# SDVX.net
KiCad netlist of a schematic drawn in Altium Designer
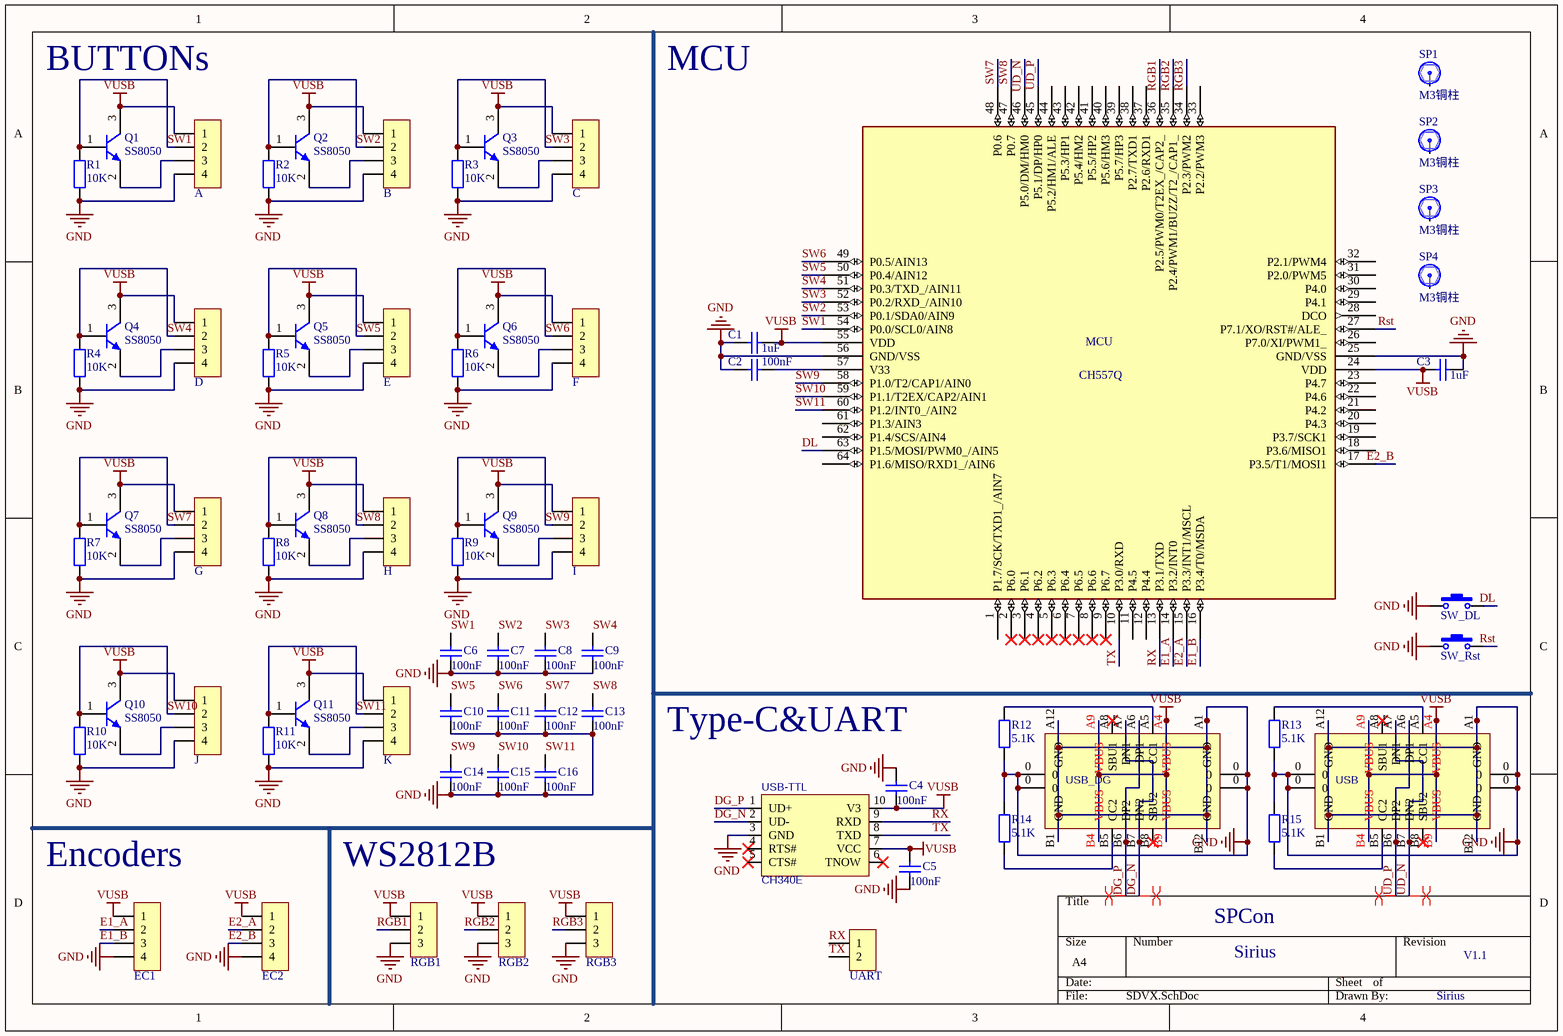
[diagram p0: SDVX.SchDoc]

(export (version "E")
  (design (tool "Eeschema 10.0.6"))
  (components
    (comp (ref "A")
      (value "HDR-1X4")
      (footprint "XH2.54-WI-4P")
      (description "4P接插件")
      (libsource (lib "5.5 - 2.54mm(100mil)连接器(XH2.54)") (part "Header 4"))
    )
    (comp (ref "B")
      (value "HDR-1X4")
      (footprint "XH2.54-WI-4P")
      (description "4P接插件")
      (libsource (lib "5.5 - 2.54mm(100mil)连接器(XH2.54)") (part "Header 4"))
    )
    (comp (ref "C")
      (value "HDR-1X4")
      (footprint "XH2.54-WI-4P")
      (description "4P接插件")
      (libsource (lib "5.5 - 2.54mm(100mil)连接器(XH2.54)") (part "Header 4"))
    )
    (comp (ref "C1")
      (value "1uF")
      (footprint "C0603_L")
      (description "贴片电容")
      (libsource (lib "0.1 - 电阻-电容-电感-电位器") (part "C"))
    )
    (comp (ref "C2")
      (value "100nF")
      (footprint "C0603_L")
      (description "贴片电容")
      (libsource (lib "0.1 - 电阻-电容-电感-电位器") (part "C"))
    )
    (comp (ref "C3")
      (value "1uF")
      (footprint "C0603_L")
      (description "贴片电容")
      (libsource (lib "0.1 - 电阻-电容-电感-电位器") (part "C"))
    )
    (comp (ref "C4")
      (value "100nF")
      (footprint "C0603_L")
      (description "贴片电容")
      (libsource (lib "0.1 - 电阻-电容-电感-电位器") (part "C"))
    )
    (comp (ref "C5")
      (value "100nF")
      (footprint "C0603_L")
      (description "贴片电容")
      (libsource (lib "0.1 - 电阻-电容-电感-电位器") (part "C"))
    )
    (comp (ref "C6")
      (value "100nF")
      (footprint "C0603_L")
      (description "贴片电容")
      (libsource (lib "0.1 - 电阻-电容-电感-电位器") (part "C"))
    )
    (comp (ref "C7")
      (value "100nF")
      (footprint "C0603_L")
      (description "贴片电容")
      (libsource (lib "0.1 - 电阻-电容-电感-电位器") (part "C"))
    )
    (comp (ref "C8")
      (value "100nF")
      (footprint "C0603_L")
      (description "贴片电容")
      (libsource (lib "0.1 - 电阻-电容-电感-电位器") (part "C"))
    )
    (comp (ref "C9")
      (value "100nF")
      (footprint "C0603_L")
      (description "贴片电容")
      (libsource (lib "0.1 - 电阻-电容-电感-电位器") (part "C"))
    )
    (comp (ref "C10")
      (value "100nF")
      (footprint "C0603_L")
      (description "贴片电容")
      (libsource (lib "0.1 - 电阻-电容-电感-电位器") (part "C"))
    )
    (comp (ref "C11")
      (value "100nF")
      (footprint "C0603_L")
      (description "贴片电容")
      (libsource (lib "0.1 - 电阻-电容-电感-电位器") (part "C"))
    )
    (comp (ref "C12")
      (value "100nF")
      (footprint "C0603_L")
      (description "贴片电容")
      (libsource (lib "0.1 - 电阻-电容-电感-电位器") (part "C"))
    )
    (comp (ref "C13")
      (value "100nF")
      (footprint "C0603_L")
      (description "贴片电容")
      (libsource (lib "0.1 - 电阻-电容-电感-电位器") (part "C"))
    )
    (comp (ref "C14")
      (value "100nF")
      (footprint "C0603_L")
      (description "贴片电容")
      (libsource (lib "0.1 - 电阻-电容-电感-电位器") (part "C"))
    )
    (comp (ref "C15")
      (value "100nF")
      (footprint "C0603_L")
      (description "贴片电容")
      (libsource (lib "0.1 - 电阻-电容-电感-电位器") (part "C"))
    )
    (comp (ref "C16")
      (value "100nF")
      (footprint "C0603_L")
      (description "贴片电容")
      (libsource (lib "0.1 - 电阻-电容-电感-电位器") (part "C"))
    )
    (comp (ref "D")
      (value "HDR-1X4")
      (footprint "XH2.54-WI-4P")
      (description "4P接插件")
      (libsource (lib "5.5 - 2.54mm(100mil)连接器(XH2.54)") (part "Header 4"))
    )
    (comp (ref "E")
      (value "HDR-1X4")
      (footprint "XH2.54-WI-4P")
      (description "4P接插件")
      (libsource (lib "5.5 - 2.54mm(100mil)连接器(XH2.54)") (part "Header 4"))
    )
    (comp (ref "EC1")
      (value "HDR-1X4")
      (footprint "XH2.54-WI-4P")
      (description "4P接插件")
      (libsource (lib "5.5 - 2.54mm(100mil)连接器(XH2.54)") (part "Header 4"))
    )
    (comp (ref "EC2")
      (value "HDR-1X4")
      (footprint "XH2.54-WI-4P")
      (description "4P接插件")
      (libsource (lib "5.5 - 2.54mm(100mil)连接器(XH2.54)") (part "Header 4"))
    )
    (comp (ref "F")
      (value "HDR-1X4")
      (footprint "XH2.54-WI-4P")
      (description "4P接插件")
      (libsource (lib "5.5 - 2.54mm(100mil)连接器(XH2.54)") (part "Header 4"))
    )
    (comp (ref "G")
      (value "HDR-1X4")
      (footprint "XH2.54-WI-4P")
      (description "4P接插件")
      (libsource (lib "5.5 - 2.54mm(100mil)连接器(XH2.54)") (part "Header 4"))
    )
    (comp (ref "H")
      (value "HDR-1X4")
      (footprint "XH2.54-WI-4P")
      (description "4P接插件")
      (libsource (lib "5.5 - 2.54mm(100mil)连接器(XH2.54)") (part "Header 4"))
    )
    (comp (ref "I")
      (value "HDR-1X4")
      (footprint "XH2.54-WI-4P")
      (description "4P接插件")
      (libsource (lib "5.5 - 2.54mm(100mil)连接器(XH2.54)") (part "Header 4"))
    )
    (comp (ref "J")
      (value "HDR-1X4")
      (footprint "XH2.54-WI-4P")
      (description "4P接插件")
      (libsource (lib "5.5 - 2.54mm(100mil)连接器(XH2.54)") (part "Header 4"))
    )
    (comp (ref "K")
      (value "HDR-1X4")
      (footprint "XH2.54-WI-4P")
      (description "4P接插件")
      (libsource (lib "5.5 - 2.54mm(100mil)连接器(XH2.54)") (part "Header 4"))
    )
    (comp (ref "MCU")
      (value "CH557Q")
      (footprint "LQFP64")
      (description "8bit MCS51 MCU with ADC & USB host 4 ports & USB device & RGB PWM & dual UART & SPI & I2C")
      (libsource (lib "CHXXX") (part "CH557Q"))
    )
    (comp (ref "Q1")
      (value "SS8050")
      (footprint "SOT23-3M")
      (description "NPN三极管")
      (libsource (lib "0.4 - 三极管-场效应管-可控硅") (part "BCP68"))
    )
    (comp (ref "Q2")
      (value "SS8050")
      (footprint "SOT23-3M")
      (description "NPN三极管")
      (libsource (lib "0.4 - 三极管-场效应管-可控硅") (part "BCP68"))
    )
    (comp (ref "Q3")
      (value "SS8050")
      (footprint "SOT23-3M")
      (description "NPN三极管")
      (libsource (lib "0.4 - 三极管-场效应管-可控硅") (part "BCP68"))
    )
    (comp (ref "Q4")
      (value "SS8050")
      (footprint "SOT23-3M")
      (description "NPN三极管")
      (libsource (lib "0.4 - 三极管-场效应管-可控硅") (part "BCP68"))
    )
    (comp (ref "Q5")
      (value "SS8050")
      (footprint "SOT23-3M")
      (description "NPN三极管")
      (libsource (lib "0.4 - 三极管-场效应管-可控硅") (part "BCP68"))
    )
    (comp (ref "Q6")
      (value "SS8050")
      (footprint "SOT23-3M")
      (description "NPN三极管")
      (libsource (lib "0.4 - 三极管-场效应管-可控硅") (part "BCP68"))
    )
    (comp (ref "Q7")
      (value "SS8050")
      (footprint "SOT23-3M")
      (description "NPN三极管")
      (libsource (lib "0.4 - 三极管-场效应管-可控硅") (part "BCP68"))
    )
    (comp (ref "Q8")
      (value "SS8050")
      (footprint "SOT23-3M")
      (description "NPN三极管")
      (libsource (lib "0.4 - 三极管-场效应管-可控硅") (part "BCP68"))
    )
    (comp (ref "Q9")
      (value "SS8050")
      (footprint "SOT23-3M")
      (description "NPN三极管")
      (libsource (lib "0.4 - 三极管-场效应管-可控硅") (part "BCP68"))
    )
    (comp (ref "Q10")
      (value "SS8050")
      (footprint "SOT23-3M")
      (description "NPN三极管")
      (libsource (lib "0.4 - 三极管-场效应管-可控硅") (part "BCP68"))
    )
    (comp (ref "Q11")
      (value "SS8050")
      (footprint "SOT23-3M")
      (description "NPN三极管")
      (libsource (lib "0.4 - 三极管-场效应管-可控硅") (part "BCP68"))
    )
    (comp (ref "R1")
      (value "10K")
      (footprint "R0603_L")
      (description "贴片电阻")
      (libsource (lib "0.1 - 电阻-电容-电感-晶振-晶体-磁珠-电位器") (part "R"))
    )
    (comp (ref "R2")
      (value "10K")
      (footprint "R0603_L")
      (description "贴片电阻")
      (libsource (lib "0.1 - 电阻-电容-电感-晶振-晶体-磁珠-电位器") (part "R"))
    )
    (comp (ref "R3")
      (value "10K")
      (footprint "R0603_L")
      (description "贴片电阻")
      (libsource (lib "0.1 - 电阻-电容-电感-晶振-晶体-磁珠-电位器") (part "R"))
    )
    (comp (ref "R4")
      (value "10K")
      (footprint "R0603_L")
      (description "贴片电阻")
      (libsource (lib "0.1 - 电阻-电容-电感-晶振-晶体-磁珠-电位器") (part "R"))
    )
    (comp (ref "R5")
      (value "10K")
      (footprint "R0603_L")
      (description "贴片电阻")
      (libsource (lib "0.1 - 电阻-电容-电感-晶振-晶体-磁珠-电位器") (part "R"))
    )
    (comp (ref "R6")
      (value "10K")
      (footprint "R0603_L")
      (description "贴片电阻")
      (libsource (lib "0.1 - 电阻-电容-电感-晶振-晶体-磁珠-电位器") (part "R"))
    )
    (comp (ref "R7")
      (value "10K")
      (footprint "R0603_L")
      (description "贴片电阻")
      (libsource (lib "0.1 - 电阻-电容-电感-晶振-晶体-磁珠-电位器") (part "R"))
    )
    (comp (ref "R8")
      (value "10K")
      (footprint "R0603_L")
      (description "贴片电阻")
      (libsource (lib "0.1 - 电阻-电容-电感-晶振-晶体-磁珠-电位器") (part "R"))
    )
    (comp (ref "R9")
      (value "10K")
      (footprint "R0603_L")
      (description "贴片电阻")
      (libsource (lib "0.1 - 电阻-电容-电感-晶振-晶体-磁珠-电位器") (part "R"))
    )
    (comp (ref "R10")
      (value "10K")
      (footprint "R0603_L")
      (description "贴片电阻")
      (libsource (lib "0.1 - 电阻-电容-电感-晶振-晶体-磁珠-电位器") (part "R"))
    )
    (comp (ref "R11")
      (value "10K")
      (footprint "R0603_L")
      (description "贴片电阻")
      (libsource (lib "0.1 - 电阻-电容-电感-晶振-晶体-磁珠-电位器") (part "R"))
    )
    (comp (ref "R12")
      (value "5.1K")
      (footprint "R0603_L")
      (description "贴片电阻")
      (libsource (lib "0.1 - 电阻-电容-电感-晶振-晶体-磁珠-电位器") (part "R"))
    )
    (comp (ref "R13")
      (value "5.1K")
      (footprint "R0603_L")
      (description "贴片电阻")
      (libsource (lib "0.1 - 电阻-电容-电感-晶振-晶体-磁珠-电位器") (part "R"))
    )
    (comp (ref "R14")
      (value "5.1K")
      (footprint "R0603_L")
      (description "贴片电阻")
      (libsource (lib "0.1 - 电阻-电容-电感-晶振-晶体-磁珠-电位器") (part "R"))
    )
    (comp (ref "R15")
      (value "5.1K")
      (footprint "R0603_L")
      (description "贴片电阻")
      (libsource (lib "0.1 - 电阻-电容-电感-晶振-晶体-磁珠-电位器") (part "R"))
    )
    (comp (ref "RGB1")
      (value "HDR-1X3")
      (footprint "HDR2.54-LI-3P")
      (description "3P接插件")
      (libsource (lib "5.5 - 2.54mm(100mil)连接器(XH2.54)") (part "Header 3"))
    )
    (comp (ref "RGB2")
      (value "HDR-1X3")
      (footprint "HDR2.54-LI-3P")
      (description "3P接插件")
      (libsource (lib "5.5 - 2.54mm(100mil)连接器(XH2.54)") (part "Header 3"))
    )
    (comp (ref "RGB3")
      (value "HDR-1X3")
      (footprint "HDR2.54-LI-3P")
      (description "3P接插件")
      (libsource (lib "5.5 - 2.54mm(100mil)连接器(XH2.54)") (part "Header 3"))
    )
    (comp (ref "SP1")
      (value "M3铜柱")
      (footprint "M3x4_L")
      (description "铜柱")
      (libsource (lib "0.5 - 按键-开关-蜂鸣器-保险丝-电池-测试点-Mark点") (part "铜柱小焊盘"))
    )
    (comp (ref "SP2")
      (value "M3铜柱")
      (footprint "M3x4_L")
      (description "铜柱")
      (libsource (lib "0.5 - 按键-开关-蜂鸣器-保险丝-电池-测试点-Mark点") (part "铜柱小焊盘"))
    )
    (comp (ref "SP3")
      (value "M3铜柱")
      (footprint "M3x4_L")
      (description "铜柱")
      (libsource (lib "0.5 - 按键-开关-蜂鸣器-保险丝-电池-测试点-Mark点") (part "铜柱小焊盘"))
    )
    (comp (ref "SP4")
      (value "M3铜柱")
      (footprint "M3x4_L")
      (description "铜柱")
      (libsource (lib "0.5 - 按键-开关-蜂鸣器-保险丝-电池-测试点-Mark点") (part "铜柱小焊盘"))
    )
    (comp (ref "SW_DL")
      (value "3x6x5")
      (footprint "SW-SMD_L4.7-W3.5-P3.35-EH")
      (description "轻触开关")
      (libsource (lib "Extra Sch") (part "SW"))
    )
    (comp (ref "SW_Rst")
      (value "3x6x5")
      (footprint "SW-SMD_L4.7-W3.5-P3.35-EH")
      (description "轻触开关")
      (libsource (lib "Extra Sch") (part "SW"))
    )
    (comp (ref "UART")
      (value "HDR-1X2")
      (footprint "HDR2.54-LI-2P")
      (description "2P接插件")
      (libsource (lib "5.5 - 2.54mm(100mil)连接器(XH2.54)") (part "Header 2"))
    )
    (comp (ref "USB")
      (value "TYPE-C 2.0 -16P")
      (footprint "USB-C-SMD_16P")
      (description "USB2.0 Type-C 16Pin  母座")
      (libsource (lib "0.8 - 以太网-音频-Type-C USB插座") (part "USB2.0_Type-C_16Pin"))
    )
    (comp (ref "USB-TTL")
      (value "CH340E")
      (footprint "MSOP-10")
      (description "USB转串口芯片，内置时钟")
      (libsource (lib "1.0 - 常见芯片") (part "CH340E"))
    )
    (comp (ref "USB_DG")
      (value "TYPE-C 2.0 -16P")
      (footprint "USB-C-SMD_16P")
      (description "USB2.0 Type-C 16Pin  母座")
      (libsource (lib "0.8 - 以太网-音频-Type-C USB插座") (part "USB2.0_Type-C_16Pin"))
    )
  )
  (nets
    (net (code "1") (name "/DG_N") (class "Default")
      (node (ref "USB-TTL") (pin "2") (pinfunction "UD-_2") (pintype "passive"))
      (node (ref "USB_DG") (pin "A7") (pinfunction "DN1_A7") (pintype "passive"))
      (node (ref "USB_DG") (pin "B7") (pinfunction "DN2_B7") (pintype "passive"))
    )
    (net (code "2") (name "/DG_P") (class "Default")
      (node (ref "USB-TTL") (pin "1") (pinfunction "UD+_1") (pintype "passive"))
      (node (ref "USB_DG") (pin "A6") (pinfunction "DP1_A6") (pintype "passive"))
      (node (ref "USB_DG") (pin "B6") (pinfunction "DP2_B6") (pintype "passive"))
    )
    (net (code "3") (name "/DL") (class "Default")
      (node (ref "MCU") (pin "63") (pinfunction "P1.5/MOSI/PWM0_/AIN5_63") (pintype "bidirectional"))
      (node (ref "SW_DL") (pin "2") (pinfunction "2_2") (pintype "passive"))
    )
    (net (code "4") (name "/E1_A") (class "Default")
      (node (ref "EC1") (pin "2") (pinfunction "2_2") (pintype "passive"))
      (node (ref "MCU") (pin "14") (pinfunction "P3.2/INT0_14") (pintype "bidirectional"))
    )
    (net (code "5") (name "/E1_B") (class "Default")
      (node (ref "EC1") (pin "3") (pinfunction "3_3") (pintype "passive"))
      (node (ref "MCU") (pin "16") (pinfunction "P3.4/T0/MSDA_16") (pintype "bidirectional"))
    )
    (net (code "6") (name "/E2_A") (class "Default")
      (node (ref "EC2") (pin "2") (pinfunction "2_2") (pintype "passive"))
      (node (ref "MCU") (pin "15") (pinfunction "P3.3/INT1/MSCL_15") (pintype "bidirectional"))
    )
    (net (code "7") (name "/E2_B") (class "Default")
      (node (ref "EC2") (pin "3") (pinfunction "3_3") (pintype "passive"))
      (node (ref "MCU") (pin "17") (pinfunction "P3.5/T1/MOSI1_17") (pintype "bidirectional"))
    )
    (net (code "8") (name "/RGB1") (class "Default")
      (node (ref "MCU") (pin "36") (pinfunction "P2.5/PWM0/T2EX_/CAP2__36") (pintype "bidirectional"))
      (node (ref "RGB1") (pin "2") (pinfunction "2_2") (pintype "passive"))
    )
    (net (code "9") (name "/RGB2") (class "Default")
      (node (ref "MCU") (pin "35") (pinfunction "P2.4/PWM1/BUZZ/T2_/CAP1__35") (pintype "bidirectional"))
      (node (ref "RGB2") (pin "2") (pinfunction "2_2") (pintype "passive"))
    )
    (net (code "10") (name "/RGB3") (class "Default")
      (node (ref "MCU") (pin "34") (pinfunction "P2.3/PWM2_34") (pintype "bidirectional"))
      (node (ref "RGB3") (pin "2") (pinfunction "2_2") (pintype "passive"))
    )
    (net (code "11") (name "/RX") (class "Default")
      (node (ref "MCU") (pin "13") (pinfunction "P3.1/TXD_13") (pintype "bidirectional"))
      (node (ref "UART") (pin "1") (pinfunction "1_1") (pintype "passive"))
      (node (ref "USB-TTL") (pin "9") (pinfunction "RXD_9") (pintype "passive"))
    )
    (net (code "12") (name "/Rst") (class "Default")
      (node (ref "MCU") (pin "27") (pinfunction "P7.1/XO/RST#/ALE__27") (pintype "bidirectional"))
      (node (ref "SW_Rst") (pin "2") (pinfunction "2_2") (pintype "passive"))
    )
    (net (code "13") (name "/SW1") (class "Default")
      (node (ref "A") (pin "2") (pinfunction "2_2") (pintype "passive"))
      (node (ref "C6") (pin "2") (pinfunction "2_2") (pintype "passive"))
      (node (ref "MCU") (pin "54") (pinfunction "P0.0/SCL0/AIN8_54") (pintype "bidirectional"))
      (node (ref "Q1") (pin "1") (pinfunction "B_1") (pintype "passive"))
      (node (ref "R1") (pin "2") (pinfunction "2_2") (pintype "passive"))
    )
    (net (code "14") (name "/SW2") (class "Default")
      (node (ref "B") (pin "2") (pinfunction "2_2") (pintype "passive"))
      (node (ref "C7") (pin "2") (pinfunction "2_2") (pintype "passive"))
      (node (ref "MCU") (pin "53") (pinfunction "P0.1/SDA0/AIN9_53") (pintype "bidirectional"))
      (node (ref "Q2") (pin "1") (pinfunction "B_1") (pintype "passive"))
      (node (ref "R2") (pin "2") (pinfunction "2_2") (pintype "passive"))
    )
    (net (code "15") (name "/SW3") (class "Default")
      (node (ref "C") (pin "2") (pinfunction "2_2") (pintype "passive"))
      (node (ref "C8") (pin "2") (pinfunction "2_2") (pintype "passive"))
      (node (ref "MCU") (pin "52") (pinfunction "P0.2/RXD_/AIN10_52") (pintype "bidirectional"))
      (node (ref "Q3") (pin "1") (pinfunction "B_1") (pintype "passive"))
      (node (ref "R3") (pin "2") (pinfunction "2_2") (pintype "passive"))
    )
    (net (code "16") (name "/SW4") (class "Default")
      (node (ref "C9") (pin "2") (pinfunction "2_2") (pintype "passive"))
      (node (ref "D") (pin "2") (pinfunction "2_2") (pintype "passive"))
      (node (ref "MCU") (pin "51") (pinfunction "P0.3/TXD_/AIN11_51") (pintype "bidirectional"))
      (node (ref "Q4") (pin "1") (pinfunction "B_1") (pintype "passive"))
      (node (ref "R4") (pin "2") (pinfunction "2_2") (pintype "passive"))
    )
    (net (code "17") (name "/SW5") (class "Default")
      (node (ref "C10") (pin "2") (pinfunction "2_2") (pintype "passive"))
      (node (ref "E") (pin "2") (pinfunction "2_2") (pintype "passive"))
      (node (ref "MCU") (pin "50") (pinfunction "P0.4/AIN12_50") (pintype "bidirectional"))
      (node (ref "Q5") (pin "1") (pinfunction "B_1") (pintype "passive"))
      (node (ref "R5") (pin "2") (pinfunction "2_2") (pintype "passive"))
    )
    (net (code "18") (name "/SW6") (class "Default")
      (node (ref "C11") (pin "2") (pinfunction "2_2") (pintype "passive"))
      (node (ref "F") (pin "2") (pinfunction "2_2") (pintype "passive"))
      (node (ref "MCU") (pin "49") (pinfunction "P0.5/AIN13_49") (pintype "bidirectional"))
      (node (ref "Q6") (pin "1") (pinfunction "B_1") (pintype "passive"))
      (node (ref "R6") (pin "2") (pinfunction "2_2") (pintype "passive"))
    )
    (net (code "19") (name "/SW7") (class "Default")
      (node (ref "C12") (pin "2") (pinfunction "2_2") (pintype "passive"))
      (node (ref "G") (pin "2") (pinfunction "2_2") (pintype "passive"))
      (node (ref "MCU") (pin "48") (pinfunction "P0.6_48") (pintype "bidirectional"))
      (node (ref "Q7") (pin "1") (pinfunction "B_1") (pintype "passive"))
      (node (ref "R7") (pin "2") (pinfunction "2_2") (pintype "passive"))
    )
    (net (code "20") (name "/SW8") (class "Default")
      (node (ref "C13") (pin "2") (pinfunction "2_2") (pintype "passive"))
      (node (ref "H") (pin "2") (pinfunction "2_2") (pintype "passive"))
      (node (ref "MCU") (pin "47") (pinfunction "P0.7_47") (pintype "bidirectional"))
      (node (ref "Q8") (pin "1") (pinfunction "B_1") (pintype "passive"))
      (node (ref "R8") (pin "2") (pinfunction "2_2") (pintype "passive"))
    )
    (net (code "21") (name "/SW9") (class "Default")
      (node (ref "C14") (pin "2") (pinfunction "2_2") (pintype "passive"))
      (node (ref "I") (pin "2") (pinfunction "2_2") (pintype "passive"))
      (node (ref "MCU") (pin "58") (pinfunction "P1.0/T2/CAP1/AIN0_58") (pintype "bidirectional"))
      (node (ref "Q9") (pin "1") (pinfunction "B_1") (pintype "passive"))
      (node (ref "R9") (pin "2") (pinfunction "2_2") (pintype "passive"))
    )
    (net (code "22") (name "/SW10") (class "Default")
      (node (ref "C15") (pin "2") (pinfunction "2_2") (pintype "passive"))
      (node (ref "J") (pin "2") (pinfunction "2_2") (pintype "passive"))
      (node (ref "MCU") (pin "59") (pinfunction "P1.1/T2EX/CAP2/AIN1_59") (pintype "bidirectional"))
      (node (ref "Q10") (pin "1") (pinfunction "B_1") (pintype "passive"))
      (node (ref "R10") (pin "2") (pinfunction "2_2") (pintype "passive"))
    )
    (net (code "23") (name "/SW11") (class "Default")
      (node (ref "C16") (pin "1") (pinfunction "1_1") (pintype "passive"))
      (node (ref "K") (pin "2") (pinfunction "2_2") (pintype "passive"))
      (node (ref "MCU") (pin "60") (pinfunction "P1.2/INT0_/AIN2_60") (pintype "bidirectional"))
      (node (ref "Q11") (pin "1") (pinfunction "B_1") (pintype "passive"))
      (node (ref "R11") (pin "2") (pinfunction "2_2") (pintype "passive"))
    )
    (net (code "24") (name "/TX") (class "Default")
      (node (ref "MCU") (pin "10") (pinfunction "P3.0/RXD_10") (pintype "bidirectional"))
      (node (ref "UART") (pin "2") (pinfunction "2_2") (pintype "passive"))
      (node (ref "USB-TTL") (pin "8") (pinfunction "TXD_8") (pintype "passive"))
    )
    (net (code "25") (name "/UD_N") (class "Default")
      (node (ref "MCU") (pin "46") (pinfunction "P5.0/DM/HM0_46") (pintype "bidirectional"))
      (node (ref "USB") (pin "A7") (pinfunction "DN1_A7") (pintype "passive"))
      (node (ref "USB") (pin "B7") (pinfunction "DN2_B7") (pintype "passive"))
    )
    (net (code "26") (name "/UD_P") (class "Default")
      (node (ref "MCU") (pin "45") (pinfunction "P5.1/DP/HP0_45") (pintype "bidirectional"))
      (node (ref "USB") (pin "A6") (pinfunction "DP1_A6") (pintype "passive"))
      (node (ref "USB") (pin "B6") (pinfunction "DP2_B6") (pintype "passive"))
    )
    (net (code "27") (name "GND") (class "Default")
      (node (ref "A") (pin "4") (pinfunction "4_4") (pintype "passive"))
      (node (ref "B") (pin "4") (pinfunction "4_4") (pintype "passive"))
      (node (ref "C") (pin "4") (pinfunction "4_4") (pintype "passive"))
      (node (ref "C1") (pin "2") (pinfunction "2_2") (pintype "passive"))
      (node (ref "C10") (pin "1") (pinfunction "1_1") (pintype "passive"))
      (node (ref "C11") (pin "1") (pinfunction "1_1") (pintype "passive"))
      (node (ref "C12") (pin "1") (pinfunction "1_1") (pintype "passive"))
      (node (ref "C13") (pin "1") (pinfunction "1_1") (pintype "passive"))
      (node (ref "C14") (pin "1") (pinfunction "1_1") (pintype "passive"))
      (node (ref "C15") (pin "1") (pinfunction "1_1") (pintype "passive"))
      (node (ref "C16") (pin "2") (pinfunction "2_2") (pintype "passive"))
      (node (ref "C2") (pin "2") (pinfunction "2_2") (pintype "passive"))
      (node (ref "C3") (pin "1") (pinfunction "1_1") (pintype "passive"))
      (node (ref "C4") (pin "2") (pinfunction "2_2") (pintype "passive"))
      (node (ref "C5") (pin "1") (pinfunction "1_1") (pintype "passive"))
      (node (ref "C6") (pin "1") (pinfunction "1_1") (pintype "passive"))
      (node (ref "C7") (pin "1") (pinfunction "1_1") (pintype "passive"))
      (node (ref "C8") (pin "1") (pinfunction "1_1") (pintype "passive"))
      (node (ref "C9") (pin "1") (pinfunction "1_1") (pintype "passive"))
      (node (ref "D") (pin "4") (pinfunction "4_4") (pintype "passive"))
      (node (ref "E") (pin "4") (pinfunction "4_4") (pintype "passive"))
      (node (ref "EC1") (pin "4") (pinfunction "4_4") (pintype "passive"))
      (node (ref "EC2") (pin "4") (pinfunction "4_4") (pintype "passive"))
      (node (ref "F") (pin "4") (pinfunction "4_4") (pintype "passive"))
      (node (ref "G") (pin "4") (pinfunction "4_4") (pintype "passive"))
      (node (ref "H") (pin "4") (pinfunction "4_4") (pintype "passive"))
      (node (ref "I") (pin "4") (pinfunction "4_4") (pintype "passive"))
      (node (ref "J") (pin "4") (pinfunction "4_4") (pintype "passive"))
      (node (ref "K") (pin "4") (pinfunction "4_4") (pintype "passive"))
      (node (ref "MCU") (pin "25") (pinfunction "GND/VSS_25") (pintype "power_in"))
      (node (ref "MCU") (pin "56") (pinfunction "GND/VSS_56") (pintype "power_in"))
      (node (ref "R1") (pin "1") (pinfunction "1_1") (pintype "passive"))
      (node (ref "R10") (pin "1") (pinfunction "1_1") (pintype "passive"))
      (node (ref "R11") (pin "1") (pinfunction "1_1") (pintype "passive"))
      (node (ref "R12") (pin "1") (pinfunction "1_1") (pintype "passive"))
      (node (ref "R13") (pin "1") (pinfunction "1_1") (pintype "passive"))
      (node (ref "R14") (pin "2") (pinfunction "2_2") (pintype "passive"))
      (node (ref "R15") (pin "2") (pinfunction "2_2") (pintype "passive"))
      (node (ref "R2") (pin "1") (pinfunction "1_1") (pintype "passive"))
      (node (ref "R3") (pin "1") (pinfunction "1_1") (pintype "passive"))
      (node (ref "R4") (pin "1") (pinfunction "1_1") (pintype "passive"))
      (node (ref "R5") (pin "1") (pinfunction "1_1") (pintype "passive"))
      (node (ref "R6") (pin "1") (pinfunction "1_1") (pintype "passive"))
      (node (ref "R7") (pin "1") (pinfunction "1_1") (pintype "passive"))
      (node (ref "R8") (pin "1") (pinfunction "1_1") (pintype "passive"))
      (node (ref "R9") (pin "1") (pinfunction "1_1") (pintype "passive"))
      (node (ref "RGB1") (pin "3") (pinfunction "3_3") (pintype "passive"))
      (node (ref "RGB2") (pin "3") (pinfunction "3_3") (pintype "passive"))
      (node (ref "RGB3") (pin "3") (pinfunction "3_3") (pintype "passive"))
      (node (ref "SW_DL") (pin "1") (pinfunction "1_1") (pintype "passive"))
      (node (ref "SW_Rst") (pin "1") (pinfunction "1_1") (pintype "passive"))
      (node (ref "USB") (pin "0") (pinfunction "0_0") (pintype "passive"))
      (node (ref "USB") (pin "A1") (pinfunction "GND_A1") (pintype "passive"))
      (node (ref "USB") (pin "A12") (pinfunction "GND_A12") (pintype "passive"))
      (node (ref "USB") (pin "B1") (pinfunction "GND_B1") (pintype "passive"))
      (node (ref "USB") (pin "B12") (pinfunction "GND_B12") (pintype "passive"))
      (node (ref "USB-TTL") (pin "3") (pinfunction "GND_3") (pintype "passive"))
      (node (ref "USB_DG") (pin "0") (pinfunction "0_0") (pintype "passive"))
      (node (ref "USB_DG") (pin "A1") (pinfunction "GND_A1") (pintype "passive"))
      (node (ref "USB_DG") (pin "A12") (pinfunction "GND_A12") (pintype "passive"))
      (node (ref "USB_DG") (pin "B1") (pinfunction "GND_B1") (pintype "passive"))
      (node (ref "USB_DG") (pin "B12") (pinfunction "GND_B12") (pintype "passive"))
    )
    (net (code "28") (name "Net-(MCU-V33)") (class "Default")
      (node (ref "C2") (pin "1") (pinfunction "1_1") (pintype "passive"))
      (node (ref "MCU") (pin "57") (pinfunction "V33_57") (pintype "power_in"))
    )
    (net (code "29") (name "Net-(Q1-E)") (class "Default")
      (node (ref "A") (pin "3") (pinfunction "3_3") (pintype "passive"))
      (node (ref "Q1") (pin "2") (pinfunction "E_2") (pintype "passive"))
    )
    (net (code "30") (name "Net-(Q2-E)") (class "Default")
      (node (ref "B") (pin "3") (pinfunction "3_3") (pintype "passive"))
      (node (ref "Q2") (pin "2") (pinfunction "E_2") (pintype "passive"))
    )
    (net (code "31") (name "Net-(Q3-E)") (class "Default")
      (node (ref "C") (pin "3") (pinfunction "3_3") (pintype "passive"))
      (node (ref "Q3") (pin "2") (pinfunction "E_2") (pintype "passive"))
    )
    (net (code "32") (name "Net-(Q4-E)") (class "Default")
      (node (ref "D") (pin "3") (pinfunction "3_3") (pintype "passive"))
      (node (ref "Q4") (pin "2") (pinfunction "E_2") (pintype "passive"))
    )
    (net (code "33") (name "Net-(Q5-E)") (class "Default")
      (node (ref "E") (pin "3") (pinfunction "3_3") (pintype "passive"))
      (node (ref "Q5") (pin "2") (pinfunction "E_2") (pintype "passive"))
    )
    (net (code "34") (name "Net-(Q6-E)") (class "Default")
      (node (ref "F") (pin "3") (pinfunction "3_3") (pintype "passive"))
      (node (ref "Q6") (pin "2") (pinfunction "E_2") (pintype "passive"))
    )
    (net (code "35") (name "Net-(Q7-E)") (class "Default")
      (node (ref "G") (pin "3") (pinfunction "3_3") (pintype "passive"))
      (node (ref "Q7") (pin "2") (pinfunction "E_2") (pintype "passive"))
    )
    (net (code "36") (name "Net-(Q8-E)") (class "Default")
      (node (ref "H") (pin "3") (pinfunction "3_3") (pintype "passive"))
      (node (ref "Q8") (pin "2") (pinfunction "E_2") (pintype "passive"))
    )
    (net (code "37") (name "Net-(Q9-E)") (class "Default")
      (node (ref "I") (pin "3") (pinfunction "3_3") (pintype "passive"))
      (node (ref "Q9") (pin "2") (pinfunction "E_2") (pintype "passive"))
    )
    (net (code "38") (name "Net-(Q10-E)") (class "Default")
      (node (ref "J") (pin "3") (pinfunction "3_3") (pintype "passive"))
      (node (ref "Q10") (pin "2") (pinfunction "E_2") (pintype "passive"))
    )
    (net (code "39") (name "Net-(Q11-E)") (class "Default")
      (node (ref "K") (pin "3") (pinfunction "3_3") (pintype "passive"))
      (node (ref "Q11") (pin "2") (pinfunction "E_2") (pintype "passive"))
    )
    (net (code "40") (name "Net-(USB-CC1)") (class "Default")
      (node (ref "R13") (pin "2") (pinfunction "2_2") (pintype "passive"))
      (node (ref "USB") (pin "A5") (pinfunction "CC1_A5") (pintype "passive"))
    )
    (net (code "41") (name "Net-(USB-CC2)") (class "Default")
      (node (ref "R15") (pin "1") (pinfunction "1_1") (pintype "passive"))
      (node (ref "USB") (pin "B5") (pinfunction "CC2_B5") (pintype "passive"))
    )
    (net (code "42") (name "Net-(USB_DG-CC1)") (class "Default")
      (node (ref "R12") (pin "2") (pinfunction "2_2") (pintype "passive"))
      (node (ref "USB_DG") (pin "A5") (pinfunction "CC1_A5") (pintype "passive"))
    )
    (net (code "43") (name "Net-(USB_DG-CC2)") (class "Default")
      (node (ref "R14") (pin "1") (pinfunction "1_1") (pintype "passive"))
      (node (ref "USB_DG") (pin "B5") (pinfunction "CC2_B5") (pintype "passive"))
    )
    (net (code "44") (name "VUSB") (class "Default")
      (node (ref "A") (pin "1") (pinfunction "1_1") (pintype "passive"))
      (node (ref "B") (pin "1") (pinfunction "1_1") (pintype "passive"))
      (node (ref "C") (pin "1") (pinfunction "1_1") (pintype "passive"))
      (node (ref "C1") (pin "1") (pinfunction "1_1") (pintype "passive"))
      (node (ref "C3") (pin "2") (pinfunction "2_2") (pintype "passive"))
      (node (ref "C4") (pin "1") (pinfunction "1_1") (pintype "passive"))
      (node (ref "C5") (pin "2") (pinfunction "2_2") (pintype "passive"))
      (node (ref "D") (pin "1") (pinfunction "1_1") (pintype "passive"))
      (node (ref "E") (pin "1") (pinfunction "1_1") (pintype "passive"))
      (node (ref "EC1") (pin "1") (pinfunction "1_1") (pintype "passive"))
      (node (ref "EC2") (pin "1") (pinfunction "1_1") (pintype "passive"))
      (node (ref "F") (pin "1") (pinfunction "1_1") (pintype "passive"))
      (node (ref "G") (pin "1") (pinfunction "1_1") (pintype "passive"))
      (node (ref "H") (pin "1") (pinfunction "1_1") (pintype "passive"))
      (node (ref "I") (pin "1") (pinfunction "1_1") (pintype "passive"))
      (node (ref "J") (pin "1") (pinfunction "1_1") (pintype "passive"))
      (node (ref "K") (pin "1") (pinfunction "1_1") (pintype "passive"))
      (node (ref "MCU") (pin "24") (pinfunction "VDD_24") (pintype "power_in"))
      (node (ref "MCU") (pin "55") (pinfunction "VDD_55") (pintype "power_in"))
      (node (ref "Q1") (pin "3") (pinfunction "C_3") (pintype "passive"))
      (node (ref "Q10") (pin "3") (pinfunction "C_3") (pintype "passive"))
      (node (ref "Q11") (pin "3") (pinfunction "C_3") (pintype "passive"))
      (node (ref "Q2") (pin "3") (pinfunction "C_3") (pintype "passive"))
      (node (ref "Q3") (pin "3") (pinfunction "C_3") (pintype "passive"))
      (node (ref "Q4") (pin "3") (pinfunction "C_3") (pintype "passive"))
      (node (ref "Q5") (pin "3") (pinfunction "C_3") (pintype "passive"))
      (node (ref "Q6") (pin "3") (pinfunction "C_3") (pintype "passive"))
      (node (ref "Q7") (pin "3") (pinfunction "C_3") (pintype "passive"))
      (node (ref "Q8") (pin "3") (pinfunction "C_3") (pintype "passive"))
      (node (ref "Q9") (pin "3") (pinfunction "C_3") (pintype "passive"))
      (node (ref "RGB1") (pin "1") (pinfunction "1_1") (pintype "passive"))
      (node (ref "RGB2") (pin "1") (pinfunction "1_1") (pintype "passive"))
      (node (ref "RGB3") (pin "1") (pinfunction "1_1") (pintype "passive"))
      (node (ref "USB") (pin "A4") (pinfunction "VBUS_A4") (pintype "passive"))
      (node (ref "USB") (pin "A9") (pinfunction "VBUS_A9") (pintype "passive"))
      (node (ref "USB") (pin "B4") (pinfunction "VBUS_B4") (pintype "passive"))
      (node (ref "USB") (pin "B9") (pinfunction "VBUS_B9") (pintype "passive"))
      (node (ref "USB-TTL") (pin "10") (pinfunction "V3_10") (pintype "passive"))
      (node (ref "USB-TTL") (pin "7") (pinfunction "VCC_7") (pintype "passive"))
      (node (ref "USB_DG") (pin "A4") (pinfunction "VBUS_A4") (pintype "passive"))
      (node (ref "USB_DG") (pin "A9") (pinfunction "VBUS_A9") (pintype "passive"))
      (node (ref "USB_DG") (pin "B4") (pinfunction "VBUS_B4") (pintype "passive"))
      (node (ref "USB_DG") (pin "B9") (pinfunction "VBUS_B9") (pintype "passive"))
    )
    (net (code "45") (name "unconnected-(MCU-DCO-Pad28)") (class "Default")
      (node (ref "MCU") (pin "28") (pinfunction "DCO_28") (pintype "output"))
    )
    (net (code "46") (name "unconnected-(MCU-P1.3{slash}AIN3-Pad61)") (class "Default")
      (node (ref "MCU") (pin "61") (pinfunction "P1.3/AIN3_61") (pintype "bidirectional"))
    )
    (net (code "47") (name "unconnected-(MCU-P1.4{slash}SCS{slash}AIN4-Pad62)") (class "Default")
      (node (ref "MCU") (pin "62") (pinfunction "P1.4/SCS/AIN4_62") (pintype "bidirectional"))
    )
    (net (code "48") (name "unconnected-(MCU-P1.6{slash}MISO{slash}RXD1_{slash}AIN6-Pad64)") (class "Default")
      (node (ref "MCU") (pin "64") (pinfunction "P1.6/MISO/RXD1_/AIN6_64") (pintype "bidirectional"))
    )
    (net (code "49") (name "unconnected-(MCU-P1.7{slash}SCK{slash}TXD1_{slash}AIN7-Pad1)") (class "Default")
      (node (ref "MCU") (pin "1") (pinfunction "P1.7/SCK/TXD1_/AIN7_1") (pintype "bidirectional"))
    )
    (net (code "50") (name "unconnected-(MCU-P2.0{slash}PWM5-Pad31)") (class "Default")
      (node (ref "MCU") (pin "31") (pinfunction "P2.0/PWM5_31") (pintype "bidirectional"))
    )
    (net (code "51") (name "unconnected-(MCU-P2.1{slash}PWM4-Pad32)") (class "Default")
      (node (ref "MCU") (pin "32") (pinfunction "P2.1/PWM4_32") (pintype "bidirectional"))
    )
    (net (code "52") (name "unconnected-(MCU-P2.2{slash}PWM3-Pad33)") (class "Default")
      (node (ref "MCU") (pin "33") (pinfunction "P2.2/PWM3_33") (pintype "bidirectional"))
    )
    (net (code "53") (name "unconnected-(MCU-P2.6{slash}RXD1-Pad37)") (class "Default")
      (node (ref "MCU") (pin "37") (pinfunction "P2.6/RXD1_37") (pintype "bidirectional"))
    )
    (net (code "54") (name "unconnected-(MCU-P2.7{slash}TXD1-Pad38)") (class "Default")
      (node (ref "MCU") (pin "38") (pinfunction "P2.7/TXD1_38") (pintype "bidirectional"))
    )
    (net (code "55") (name "unconnected-(MCU-P3.6{slash}MISO1-Pad18)") (class "Default")
      (node (ref "MCU") (pin "18") (pinfunction "P3.6/MISO1_18") (pintype "bidirectional"))
    )
    (net (code "56") (name "unconnected-(MCU-P3.7{slash}SCK1-Pad19)") (class "Default")
      (node (ref "MCU") (pin "19") (pinfunction "P3.7/SCK1_19") (pintype "bidirectional"))
    )
    (net (code "57") (name "unconnected-(MCU-P4.0-Pad30)") (class "Default")
      (node (ref "MCU") (pin "30") (pinfunction "P4.0_30") (pintype "bidirectional"))
    )
    (net (code "58") (name "unconnected-(MCU-P4.1-Pad29)") (class "Default")
      (node (ref "MCU") (pin "29") (pinfunction "P4.1_29") (pintype "bidirectional"))
    )
    (net (code "59") (name "unconnected-(MCU-P4.2-Pad21)") (class "Default")
      (node (ref "MCU") (pin "21") (pinfunction "P4.2_21") (pintype "bidirectional"))
    )
    (net (code "60") (name "unconnected-(MCU-P4.3-Pad20)") (class "Default")
      (node (ref "MCU") (pin "20") (pinfunction "P4.3_20") (pintype "bidirectional"))
    )
    (net (code "61") (name "unconnected-(MCU-P4.4-Pad12)") (class "Default")
      (node (ref "MCU") (pin "12") (pinfunction "P4.4_12") (pintype "bidirectional"))
    )
    (net (code "62") (name "unconnected-(MCU-P4.5-Pad11)") (class "Default")
      (node (ref "MCU") (pin "11") (pinfunction "P4.5_11") (pintype "bidirectional"))
    )
    (net (code "63") (name "unconnected-(MCU-P4.6-Pad22)") (class "Default")
      (node (ref "MCU") (pin "22") (pinfunction "P4.6_22") (pintype "bidirectional"))
    )
    (net (code "64") (name "unconnected-(MCU-P4.7-Pad23)") (class "Default")
      (node (ref "MCU") (pin "23") (pinfunction "P4.7_23") (pintype "bidirectional"))
    )
    (net (code "65") (name "unconnected-(MCU-P5.2{slash}HM1{slash}ALE-Pad44)") (class "Default")
      (node (ref "MCU") (pin "44") (pinfunction "P5.2/HM1/ALE_44") (pintype "bidirectional"))
    )
    (net (code "66") (name "unconnected-(MCU-P5.3{slash}HP1-Pad43)") (class "Default")
      (node (ref "MCU") (pin "43") (pinfunction "P5.3/HP1_43") (pintype "bidirectional"))
    )
    (net (code "67") (name "unconnected-(MCU-P5.4{slash}HM2-Pad42)") (class "Default")
      (node (ref "MCU") (pin "42") (pinfunction "P5.4/HM2_42") (pintype "bidirectional"))
    )
    (net (code "68") (name "unconnected-(MCU-P5.5{slash}HP2-Pad41)") (class "Default")
      (node (ref "MCU") (pin "41") (pinfunction "P5.5/HP2_41") (pintype "bidirectional"))
    )
    (net (code "69") (name "unconnected-(MCU-P5.6{slash}HM3-Pad40)") (class "Default")
      (node (ref "MCU") (pin "40") (pinfunction "P5.6/HM3_40") (pintype "bidirectional"))
    )
    (net (code "70") (name "unconnected-(MCU-P5.7{slash}HP3-Pad39)") (class "Default")
      (node (ref "MCU") (pin "39") (pinfunction "P5.7/HP3_39") (pintype "bidirectional"))
    )
    (net (code "71") (name "unconnected-(MCU-P6.0-Pad2)") (class "Default")
      (node (ref "MCU") (pin "2") (pinfunction "P6.0_2") (pintype "bidirectional+no_connect"))
    )
    (net (code "72") (name "unconnected-(MCU-P6.1-Pad3)") (class "Default")
      (node (ref "MCU") (pin "3") (pinfunction "P6.1_3") (pintype "bidirectional+no_connect"))
    )
    (net (code "73") (name "unconnected-(MCU-P6.2-Pad4)") (class "Default")
      (node (ref "MCU") (pin "4") (pinfunction "P6.2_4") (pintype "bidirectional+no_connect"))
    )
    (net (code "74") (name "unconnected-(MCU-P6.3-Pad5)") (class "Default")
      (node (ref "MCU") (pin "5") (pinfunction "P6.3_5") (pintype "bidirectional+no_connect"))
    )
    (net (code "75") (name "unconnected-(MCU-P6.4-Pad6)") (class "Default")
      (node (ref "MCU") (pin "6") (pinfunction "P6.4_6") (pintype "bidirectional+no_connect"))
    )
    (net (code "76") (name "unconnected-(MCU-P6.5-Pad7)") (class "Default")
      (node (ref "MCU") (pin "7") (pinfunction "P6.5_7") (pintype "bidirectional+no_connect"))
    )
    (net (code "77") (name "unconnected-(MCU-P6.6-Pad8)") (class "Default")
      (node (ref "MCU") (pin "8") (pinfunction "P6.6_8") (pintype "bidirectional+no_connect"))
    )
    (net (code "78") (name "unconnected-(MCU-P6.7-Pad9)") (class "Default")
      (node (ref "MCU") (pin "9") (pinfunction "P6.7_9") (pintype "bidirectional+no_connect"))
    )
    (net (code "79") (name "unconnected-(MCU-P7.0{slash}XI{slash}PWM1_-Pad26)") (class "Default")
      (node (ref "MCU") (pin "26") (pinfunction "P7.0/XI/PWM1__26") (pintype "bidirectional"))
    )
    (net (code "80") (name "unconnected-(SP1-Pad1)") (class "Default")
      (node (ref "SP1") (pin "1") (pinfunction "1_1") (pintype "passive"))
    )
    (net (code "81") (name "unconnected-(SP2-Pad1)") (class "Default")
      (node (ref "SP2") (pin "1") (pinfunction "1_1") (pintype "passive"))
    )
    (net (code "82") (name "unconnected-(SP3-Pad1)") (class "Default")
      (node (ref "SP3") (pin "1") (pinfunction "1_1") (pintype "passive"))
    )
    (net (code "83") (name "unconnected-(SP4-Pad1)") (class "Default")
      (node (ref "SP4") (pin "1") (pinfunction "1_1") (pintype "passive"))
    )
    (net (code "84") (name "unconnected-(USB-SBU1-PadA8)") (class "Default")
      (node (ref "USB") (pin "A8") (pinfunction "SBU1_A8") (pintype "passive+no_connect"))
    )
    (net (code "85") (name "unconnected-(USB-SBU2-PadB8)") (class "Default")
      (node (ref "USB") (pin "B8") (pinfunction "SBU2_B8") (pintype "passive+no_connect"))
    )
    (net (code "86") (name "unconnected-(USB-TTL-CTS#-Pad5)") (class "Default")
      (node (ref "USB-TTL") (pin "5") (pinfunction "CTS#_5") (pintype "passive+no_connect"))
    )
    (net (code "87") (name "unconnected-(USB-TTL-RTS#-Pad4)") (class "Default")
      (node (ref "USB-TTL") (pin "4") (pinfunction "RTS#_4") (pintype "passive+no_connect"))
    )
    (net (code "88") (name "unconnected-(USB-TTL-TNOW-Pad6)") (class "Default")
      (node (ref "USB-TTL") (pin "6") (pinfunction "TNOW_6") (pintype "passive+no_connect"))
    )
    (net (code "89") (name "unconnected-(USB_DG-SBU1-PadA8)") (class "Default")
      (node (ref "USB_DG") (pin "A8") (pinfunction "SBU1_A8") (pintype "passive+no_connect"))
    )
    (net (code "90") (name "unconnected-(USB_DG-SBU2-PadB8)") (class "Default")
      (node (ref "USB_DG") (pin "B8") (pinfunction "SBU2_B8") (pintype "passive+no_connect"))
    )
  )
)
